# car_msp_breakouts.net
KiCad netlist of a schematic drawn in Altium Designer
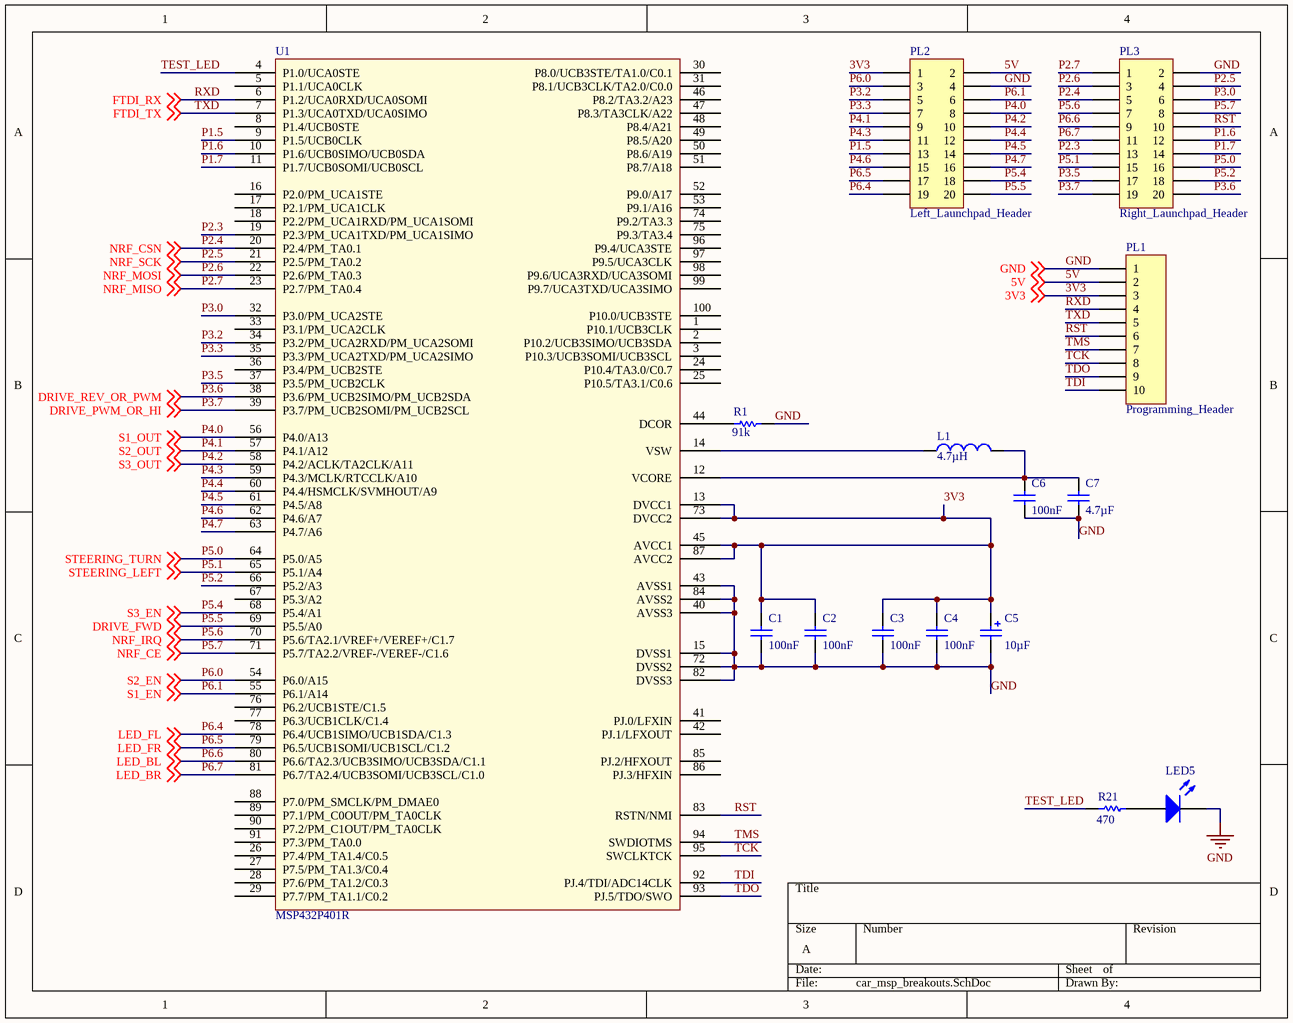
[diagram p0: car_msp_breakouts.SchDoc]

(export (version "E")
  (design (tool "Eeschema 10.0.6"))
  (components
    (comp (ref "C1")
      (value "100nF")
      (footprint "0805-C")
      (description "Capacitor")
      (fields (field (name "Comment") "Cap") (field (name "PUBLISHER") "Altium Limited"))
      (libsource (lib "Miscellaneous Devices") (part "Cap"))
    )
    (comp (ref "C2")
      (value "100nF")
      (footprint "0805-C")
      (description "Capacitor")
      (fields (field (name "Comment") "Cap") (field (name "PUBLISHER") "Altium Limited"))
      (libsource (lib "Miscellaneous Devices") (part "Cap"))
    )
    (comp (ref "C3")
      (value "100nF")
      (footprint "0805-C")
      (description "Capacitor")
      (fields (field (name "Comment") "Cap") (field (name "PUBLISHER") "Altium Limited"))
      (libsource (lib "Miscellaneous Devices") (part "Cap"))
    )
    (comp (ref "C4")
      (value "100nF")
      (footprint "0805-C")
      (description "Capacitor")
      (fields (field (name "Comment") "Cap") (field (name "PUBLISHER") "Altium Limited"))
      (libsource (lib "Miscellaneous Devices") (part "Cap"))
    )
    (comp (ref "C5")
      (value "10µF")
      (footprint "0805-TC")
      (description "Polarized Capacitor (Radial)")
      (fields (field (name "Comment") "Cap Pol1") (field (name "PUBLISHER") "Altium Limited"))
      (libsource (lib "Miscellaneous Devices") (part "Cap Pol1"))
    )
    (comp (ref "C6")
      (value "100nF")
      (footprint "0805-C")
      (description "Capacitor")
      (fields (field (name "Comment") "Cap") (field (name "PUBLISHER") "Altium Limited"))
      (libsource (lib "Miscellaneous Devices") (part "Cap"))
    )
    (comp (ref "C7")
      (value "4.7µF")
      (footprint "0805-C")
      (description "Capacitor")
      (fields (field (name "Comment") "Cap") (field (name "PUBLISHER") "Altium Limited"))
      (libsource (lib "Miscellaneous Devices") (part "Cap"))
    )
    (comp (ref "L1")
      (value "4.7µH")
      (footprint "0805-L")
      (description "Inductor")
      (fields (field (name "PUBLISHER") "Altium Limited"))
      (libsource (lib "Miscellaneous Devices") (part "Inductor"))
    )
    (comp (ref "LED5")
      (value "LED2")
      (footprint "0805-LED")
      (description "Typical RED, GREEN, YELLOW, AMBER GaAs LED")
      (fields (field (name "PUBLISHER") "Altium Limited"))
      (libsource (lib "Miscellaneous Devices") (part "LED2"))
    )
    (comp (ref "PL1")
      (value "Programming_Header")
      (footprint "HDR1X10")
      (description "Header, 10-Pin")
      (fields (field (name "PUBLISHER") "Altium Limited"))
      (libsource (lib "Miscellaneous Connectors") (part "Header 10"))
    )
    (comp (ref "PL2")
      (value "Left_Launchpad_Header")
      (footprint "HDR2X10")
      (description "Header, 10-Pin, Dual row")
      (fields (field (name "PUBLISHER") "Altium Limited"))
      (libsource (lib "Miscellaneous Connectors") (part "Header 10X2"))
    )
    (comp (ref "PL3")
      (value "Right_Launchpad_Header")
      (footprint "HDR2X10")
      (description "Header, 10-Pin, Dual row")
      (fields (field (name "PUBLISHER") "Altium Limited"))
      (libsource (lib "Miscellaneous Connectors") (part "Header 10X2"))
    )
    (comp (ref "R1")
      (value "91k")
      (footprint "0805-R")
      (description "Resistor")
      (fields (field (name "Comment") "Res1") (field (name "PUBLISHER") "Altium Limited"))
      (libsource (lib "Miscellaneous Devices") (part "Res1"))
    )
    (comp (ref "R21")
      (value "470")
      (footprint "0805-R")
      (description "Resistor")
      (fields (field (name "Comment") "Res1") (field (name "PUBLISHER") "Altium Limited"))
      (libsource (lib "Miscellaneous Devices") (part "Res1"))
    )
    (comp (ref "U1")
      (value "MSP432P401R")
      (footprint "TSQFP50P1600X1600X160-100N")
      (libsource (lib "MSP432") (part "MSP432"))
    )
  )
  (nets
    (net (code "1") (name "/P1.5") (class "Default")
      (node (ref "PL2") (pin "13") (pinfunction "13_13") (pintype "passive"))
      (node (ref "U1") (pin "9") (pinfunction "P1.5/UCB0CLK_9") (pintype "passive"))
    )
    (net (code "2") (name "/P1.6") (class "Default")
      (node (ref "PL3") (pin "12") (pinfunction "12_12") (pintype "passive"))
      (node (ref "U1") (pin "10") (pinfunction "P1.6/UCB0SIMO/UCB0SDA_10") (pintype "passive"))
    )
    (net (code "3") (name "/P1.7") (class "Default")
      (node (ref "PL3") (pin "14") (pinfunction "14_14") (pintype "passive"))
      (node (ref "U1") (pin "11") (pinfunction "P1.7/UCB0SOMI/UCB0SCL_11") (pintype "passive"))
    )
    (net (code "4") (name "/P2.3") (class "Default")
      (node (ref "PL3") (pin "13") (pinfunction "13_13") (pintype "passive"))
      (node (ref "U1") (pin "19") (pinfunction "P2.3/PM_UCA1TXD/PM_UCA1SIMO_19") (pintype "passive"))
    )
    (net (code "5") (name "/P3.0") (class "Default")
      (node (ref "PL3") (pin "6") (pinfunction "6_6") (pintype "passive"))
      (node (ref "U1") (pin "32") (pinfunction "P3.0/PM_UCA2STE_32") (pintype "passive"))
    )
    (net (code "6") (name "/P3.2") (class "Default")
      (node (ref "PL2") (pin "5") (pinfunction "5_5") (pintype "passive"))
      (node (ref "U1") (pin "34") (pinfunction "P3.2/PM_UCA2RXD/PM_UCA2SOMI_34") (pintype "passive"))
    )
    (net (code "7") (name "/P3.3") (class "Default")
      (node (ref "PL2") (pin "7") (pinfunction "7_7") (pintype "passive"))
      (node (ref "U1") (pin "35") (pinfunction "P3.3/PM_UCA2TXD/PM_UCA2SIMO_35") (pintype "passive"))
    )
    (net (code "8") (name "/P3.5") (class "Default")
      (node (ref "PL3") (pin "17") (pinfunction "17_17") (pintype "passive"))
      (node (ref "U1") (pin "37") (pinfunction "P3.5/PM_UCB2CLK_37") (pintype "passive"))
    )
    (net (code "9") (name "/P4.3") (class "Default")
      (node (ref "PL2") (pin "11") (pinfunction "11_11") (pintype "passive"))
      (node (ref "U1") (pin "59") (pinfunction "P4.3/MCLK/RTCCLK/A10_59") (pintype "passive"))
    )
    (net (code "10") (name "/P4.4") (class "Default")
      (node (ref "PL2") (pin "12") (pinfunction "12_12") (pintype "passive"))
      (node (ref "U1") (pin "60") (pinfunction "P4.4/HSMCLK/SVMHOUT/A9_60") (pintype "passive"))
    )
    (net (code "11") (name "/P4.5") (class "Default")
      (node (ref "PL2") (pin "14") (pinfunction "14_14") (pintype "passive"))
      (node (ref "U1") (pin "61") (pinfunction "P4.5/A8_61") (pintype "passive"))
    )
    (net (code "12") (name "/P4.6") (class "Default")
      (node (ref "PL2") (pin "15") (pinfunction "15_15") (pintype "passive"))
      (node (ref "U1") (pin "62") (pinfunction "P4.6/A7_62") (pintype "passive"))
    )
    (net (code "13") (name "/P4.7") (class "Default")
      (node (ref "PL2") (pin "16") (pinfunction "16_16") (pintype "passive"))
      (node (ref "U1") (pin "63") (pinfunction "P4.7/A6_63") (pintype "passive"))
    )
    (net (code "14") (name "/P5.2") (class "Default")
      (node (ref "PL3") (pin "18") (pinfunction "18_18") (pintype "passive"))
      (node (ref "U1") (pin "66") (pinfunction "P5.2/A3_66") (pintype "passive"))
    )
    (net (code "15") (name "/RST") (class "Default")
      (node (ref "PL1") (pin "6") (pinfunction "6_6") (pintype "passive"))
      (node (ref "PL3") (pin "10") (pinfunction "10_10") (pintype "passive"))
      (node (ref "U1") (pin "83") (pinfunction "RSTN/NMI_83") (pintype "passive"))
    )
    (net (code "16") (name "/TCK") (class "Default")
      (node (ref "PL1") (pin "8") (pinfunction "8_8") (pintype "passive"))
      (node (ref "U1") (pin "95") (pinfunction "SWCLKTCK_95") (pintype "passive"))
    )
    (net (code "17") (name "/TDI") (class "Default")
      (node (ref "PL1") (pin "10") (pinfunction "10_10") (pintype "passive"))
      (node (ref "U1") (pin "92") (pinfunction "PJ.4/TDI/ADC14CLK_92") (pintype "passive"))
    )
    (net (code "18") (name "/TDO") (class "Default")
      (node (ref "PL1") (pin "9") (pinfunction "9_9") (pintype "passive"))
      (node (ref "U1") (pin "93") (pinfunction "PJ.5/TDO/SWO_93") (pintype "passive"))
    )
    (net (code "19") (name "/TEST_LED") (class "Default")
      (node (ref "R21") (pin "1") (pinfunction "1_1") (pintype "passive"))
      (node (ref "U1") (pin "4") (pinfunction "P1.0/UCA0STE_4") (pintype "passive"))
    )
    (net (code "20") (name "/TMS") (class "Default")
      (node (ref "PL1") (pin "7") (pinfunction "7_7") (pintype "passive"))
      (node (ref "U1") (pin "94") (pinfunction "SWDIOTMS_94") (pintype "passive"))
    )
    (net (code "21") (name "3V3") (class "Default")
      (node (ref "C1") (pin "2") (pinfunction "2_2") (pintype "passive"))
      (node (ref "C2") (pin "2") (pinfunction "2_2") (pintype "passive"))
      (node (ref "C3") (pin "2") (pinfunction "2_2") (pintype "passive"))
      (node (ref "C4") (pin "2") (pinfunction "2_2") (pintype "passive"))
      (node (ref "C5") (pin "1") (pinfunction "1_1") (pintype "passive"))
      (node (ref "PL1") (pin "3") (pinfunction "3_3") (pintype "passive"))
      (node (ref "PL2") (pin "1") (pinfunction "1_1") (pintype "passive"))
      (node (ref "U1") (pin "13") (pinfunction "DVCC1_13") (pintype "passive"))
      (node (ref "U1") (pin "45") (pinfunction "AVCC1_45") (pintype "passive"))
      (node (ref "U1") (pin "73") (pinfunction "DVCC2_73") (pintype "passive"))
      (node (ref "U1") (pin "87") (pinfunction "AVCC2_87") (pintype "passive"))
    )
    (net (code "22") (name "5V") (class "Default")
      (node (ref "PL1") (pin "2") (pinfunction "2_2") (pintype "passive"))
      (node (ref "PL2") (pin "2") (pinfunction "2_2") (pintype "passive"))
    )
    (net (code "23") (name "DRIVE_FWD") (class "Default")
      (node (ref "PL2") (pin "20") (pinfunction "20_20") (pintype "passive"))
      (node (ref "U1") (pin "69") (pinfunction "P5.5/A0_69") (pintype "passive"))
    )
    (net (code "24") (name "DRIVE_PWM_OR_HI") (class "Default")
      (node (ref "PL3") (pin "19") (pinfunction "19_19") (pintype "passive"))
      (node (ref "U1") (pin "39") (pinfunction "P3.7/PM_UCB2SOMI/PM_UCB2SCL_39") (pintype "passive"))
    )
    (net (code "25") (name "DRIVE_REV_OR_PWM") (class "Default")
      (node (ref "PL3") (pin "20") (pinfunction "20_20") (pintype "passive"))
      (node (ref "U1") (pin "38") (pinfunction "P3.6/PM_UCB2SIMO/PM_UCB2SDA_38") (pintype "passive"))
    )
    (net (code "26") (name "FTDI_RX") (class "Default")
      (node (ref "PL1") (pin "4") (pinfunction "4_4") (pintype "passive"))
      (node (ref "U1") (pin "6") (pinfunction "P1.2/UCA0RXD/UCA0SOMI_6") (pintype "passive"))
    )
    (net (code "27") (name "FTDI_TX") (class "Default")
      (node (ref "PL1") (pin "5") (pinfunction "5_5") (pintype "passive"))
      (node (ref "U1") (pin "7") (pinfunction "P1.3/UCA0TXD/UCA0SIMO_7") (pintype "passive"))
    )
    (net (code "28") (name "GND") (class "Default")
      (node (ref "C1") (pin "1") (pinfunction "1_1") (pintype "passive"))
      (node (ref "C2") (pin "1") (pinfunction "1_1") (pintype "passive"))
      (node (ref "C3") (pin "1") (pinfunction "1_1") (pintype "passive"))
      (node (ref "C4") (pin "1") (pinfunction "1_1") (pintype "passive"))
      (node (ref "C5") (pin "2") (pinfunction "2_2") (pintype "passive"))
      (node (ref "C6") (pin "1") (pinfunction "1_1") (pintype "passive"))
      (node (ref "C7") (pin "1") (pinfunction "1_1") (pintype "passive"))
      (node (ref "LED5") (pin "2") (pinfunction "K_2") (pintype "passive"))
      (node (ref "PL1") (pin "1") (pinfunction "1_1") (pintype "passive"))
      (node (ref "PL2") (pin "4") (pinfunction "4_4") (pintype "passive"))
      (node (ref "PL3") (pin "2") (pinfunction "2_2") (pintype "passive"))
      (node (ref "R1") (pin "2") (pinfunction "2_2") (pintype "passive"))
      (node (ref "U1") (pin "15") (pinfunction "DVSS1_15") (pintype "passive"))
      (node (ref "U1") (pin "40") (pinfunction "AVSS3_40") (pintype "passive"))
      (node (ref "U1") (pin "43") (pinfunction "AVSS1_43") (pintype "passive"))
      (node (ref "U1") (pin "72") (pinfunction "DVSS2_72") (pintype "passive"))
      (node (ref "U1") (pin "82") (pinfunction "DVSS3_82") (pintype "passive"))
      (node (ref "U1") (pin "84") (pinfunction "AVSS2_84") (pintype "passive"))
    )
    (net (code "29") (name "LED_BL") (class "Default")
      (node (ref "PL3") (pin "9") (pinfunction "9_9") (pintype "passive"))
      (node (ref "U1") (pin "80") (pinfunction "P6.6/TA2.3/UCB3SIMO/UCB3SDA/C1.1_80") (pintype "passive"))
    )
    (net (code "30") (name "LED_BR") (class "Default")
      (node (ref "PL3") (pin "11") (pinfunction "11_11") (pintype "passive"))
      (node (ref "U1") (pin "81") (pinfunction "P6.7/TA2.4/UCB3SOMI/UCB3SCL/C1.0_81") (pintype "passive"))
    )
    (net (code "31") (name "LED_FL") (class "Default")
      (node (ref "PL2") (pin "19") (pinfunction "19_19") (pintype "passive"))
      (node (ref "U1") (pin "78") (pinfunction "P6.4/UCB1SIMO/UCB1SDA/C1.3_78") (pintype "passive"))
    )
    (net (code "32") (name "LED_FR") (class "Default")
      (node (ref "PL2") (pin "17") (pinfunction "17_17") (pintype "passive"))
      (node (ref "U1") (pin "79") (pinfunction "P6.5/UCB1SOMI/UCB1SCL/C1.2_79") (pintype "passive"))
    )
    (net (code "33") (name "NRF_CE") (class "Default")
      (node (ref "PL3") (pin "8") (pinfunction "8_8") (pintype "passive"))
      (node (ref "U1") (pin "71") (pinfunction "P5.7/TA2.2/VREF-/VEREF-/C1.6_71") (pintype "passive"))
    )
    (net (code "34") (name "NRF_CSN") (class "Default")
      (node (ref "PL3") (pin "5") (pinfunction "5_5") (pintype "passive"))
      (node (ref "U1") (pin "20") (pinfunction "P2.4/PM_TA0.1_20") (pintype "passive"))
    )
    (net (code "35") (name "NRF_IRQ") (class "Default")
      (node (ref "PL3") (pin "7") (pinfunction "7_7") (pintype "passive"))
      (node (ref "U1") (pin "70") (pinfunction "P5.6/TA2.1/VREF+/VEREF+/C1.7_70") (pintype "passive"))
    )
    (net (code "36") (name "NRF_MISO") (class "Default")
      (node (ref "PL3") (pin "1") (pinfunction "1_1") (pintype "passive"))
      (node (ref "U1") (pin "23") (pinfunction "P2.7/PM_TA0.4_23") (pintype "passive"))
    )
    (net (code "37") (name "NRF_MOSI") (class "Default")
      (node (ref "PL3") (pin "3") (pinfunction "3_3") (pintype "passive"))
      (node (ref "U1") (pin "22") (pinfunction "P2.6/PM_TA0.3_22") (pintype "passive"))
    )
    (net (code "38") (name "NRF_SCK") (class "Default")
      (node (ref "PL3") (pin "4") (pinfunction "4_4") (pintype "passive"))
      (node (ref "U1") (pin "21") (pinfunction "P2.5/PM_TA0.2_21") (pintype "passive"))
    )
    (net (code "39") (name "Net-(LED5-A)") (class "Default")
      (node (ref "LED5") (pin "1") (pinfunction "A_1") (pintype "passive"))
      (node (ref "R21") (pin "2") (pinfunction "2_2") (pintype "passive"))
    )
    (net (code "40") (name "Net-(U1-DCOR)") (class "Default")
      (node (ref "R1") (pin "1") (pinfunction "1_1") (pintype "passive"))
      (node (ref "U1") (pin "44") (pinfunction "DCOR_44") (pintype "passive"))
    )
    (net (code "41") (name "Net-(U1-VCORE)") (class "Default")
      (node (ref "C6") (pin "2") (pinfunction "2_2") (pintype "passive"))
      (node (ref "C7") (pin "2") (pinfunction "2_2") (pintype "passive"))
      (node (ref "L1") (pin "2") (pinfunction "2_2") (pintype "passive"))
      (node (ref "U1") (pin "12") (pinfunction "VCORE_12") (pintype "passive"))
    )
    (net (code "42") (name "Net-(U1-VSW)") (class "Default")
      (node (ref "L1") (pin "1") (pinfunction "1_1") (pintype "passive"))
      (node (ref "U1") (pin "14") (pinfunction "VSW_14") (pintype "passive"))
    )
    (net (code "43") (name "S1_EN") (class "Default")
      (node (ref "PL2") (pin "6") (pinfunction "6_6") (pintype "passive"))
      (node (ref "U1") (pin "55") (pinfunction "P6.1/A14_55") (pintype "passive"))
    )
    (net (code "44") (name "S1_OUT") (class "Default")
      (node (ref "PL2") (pin "8") (pinfunction "8_8") (pintype "passive"))
      (node (ref "U1") (pin "56") (pinfunction "P4.0/A13_56") (pintype "passive"))
    )
    (net (code "45") (name "S2_EN") (class "Default")
      (node (ref "PL2") (pin "3") (pinfunction "3_3") (pintype "passive"))
      (node (ref "U1") (pin "54") (pinfunction "P6.0/A15_54") (pintype "passive"))
    )
    (net (code "46") (name "S2_OUT") (class "Default")
      (node (ref "PL2") (pin "9") (pinfunction "9_9") (pintype "passive"))
      (node (ref "U1") (pin "57") (pinfunction "P4.1/A12_57") (pintype "passive"))
    )
    (net (code "47") (name "S3_EN") (class "Default")
      (node (ref "PL2") (pin "18") (pinfunction "18_18") (pintype "passive"))
      (node (ref "U1") (pin "68") (pinfunction "P5.4/A1_68") (pintype "passive"))
    )
    (net (code "48") (name "S3_OUT") (class "Default")
      (node (ref "PL2") (pin "10") (pinfunction "10_10") (pintype "passive"))
      (node (ref "U1") (pin "58") (pinfunction "P4.2/ACLK/TA2CLK/A11_58") (pintype "passive"))
    )
    (net (code "49") (name "STEERING_LEFT") (class "Default")
      (node (ref "PL3") (pin "15") (pinfunction "15_15") (pintype "passive"))
      (node (ref "U1") (pin "65") (pinfunction "P5.1/A4_65") (pintype "passive"))
    )
    (net (code "50") (name "STEERING_TURN") (class "Default")
      (node (ref "PL3") (pin "16") (pinfunction "16_16") (pintype "passive"))
      (node (ref "U1") (pin "64") (pinfunction "P5.0/A5_64") (pintype "passive"))
    )
    (net (code "51") (name "unconnected-(U1-P1.1{slash}UCA0CLK-Pad5)") (class "Default")
      (node (ref "U1") (pin "5") (pinfunction "P1.1/UCA0CLK_5") (pintype "passive"))
    )
    (net (code "52") (name "unconnected-(U1-P1.4{slash}UCB0STE-Pad8)") (class "Default")
      (node (ref "U1") (pin "8") (pinfunction "P1.4/UCB0STE_8") (pintype "passive"))
    )
    (net (code "53") (name "unconnected-(U1-P2.0{slash}PM_UCA1STE-Pad16)") (class "Default")
      (node (ref "U1") (pin "16") (pinfunction "P2.0/PM_UCA1STE_16") (pintype "passive"))
    )
    (net (code "54") (name "unconnected-(U1-P2.1{slash}PM_UCA1CLK-Pad17)") (class "Default")
      (node (ref "U1") (pin "17") (pinfunction "P2.1/PM_UCA1CLK_17") (pintype "passive"))
    )
    (net (code "55") (name "unconnected-(U1-P2.2{slash}PM_UCA1RXD{slash}PM_UCA1SOMI-Pad18)") (class "Default")
      (node (ref "U1") (pin "18") (pinfunction "P2.2/PM_UCA1RXD/PM_UCA1SOMI_18") (pintype "passive"))
    )
    (net (code "56") (name "unconnected-(U1-P3.1{slash}PM_UCA2CLK-Pad33)") (class "Default")
      (node (ref "U1") (pin "33") (pinfunction "P3.1/PM_UCA2CLK_33") (pintype "passive"))
    )
    (net (code "57") (name "unconnected-(U1-P3.4{slash}PM_UCB2STE-Pad36)") (class "Default")
      (node (ref "U1") (pin "36") (pinfunction "P3.4/PM_UCB2STE_36") (pintype "passive"))
    )
    (net (code "58") (name "unconnected-(U1-P5.3{slash}A2-Pad67)") (class "Default")
      (node (ref "U1") (pin "67") (pinfunction "P5.3/A2_67") (pintype "passive"))
    )
    (net (code "59") (name "unconnected-(U1-P6.2{slash}UCB1STE{slash}C1.5-Pad76)") (class "Default")
      (node (ref "U1") (pin "76") (pinfunction "P6.2/UCB1STE/C1.5_76") (pintype "passive"))
    )
    (net (code "60") (name "unconnected-(U1-P6.3{slash}UCB1CLK{slash}C1.4-Pad77)") (class "Default")
      (node (ref "U1") (pin "77") (pinfunction "P6.3/UCB1CLK/C1.4_77") (pintype "passive"))
    )
    (net (code "61") (name "unconnected-(U1-P7.0{slash}PM_SMCLK{slash}PM_DMAE0-Pad88)") (class "Default")
      (node (ref "U1") (pin "88") (pinfunction "P7.0/PM_SMCLK/PM_DMAE0_88") (pintype "passive"))
    )
    (net (code "62") (name "unconnected-(U1-P7.1{slash}PM_C0OUT{slash}PM_TA0CLK-Pad89)") (class "Default")
      (node (ref "U1") (pin "89") (pinfunction "P7.1/PM_C0OUT/PM_TA0CLK_89") (pintype "passive"))
    )
    (net (code "63") (name "unconnected-(U1-P7.2{slash}PM_C1OUT{slash}PM_TA0CLK-Pad90)") (class "Default")
      (node (ref "U1") (pin "90") (pinfunction "P7.2/PM_C1OUT/PM_TA0CLK_90") (pintype "passive"))
    )
    (net (code "64") (name "unconnected-(U1-P7.3{slash}PM_TA0.0-Pad91)") (class "Default")
      (node (ref "U1") (pin "91") (pinfunction "P7.3/PM_TA0.0_91") (pintype "passive"))
    )
    (net (code "65") (name "unconnected-(U1-P7.4{slash}PM_TA1.4{slash}C0.5-Pad26)") (class "Default")
      (node (ref "U1") (pin "26") (pinfunction "P7.4/PM_TA1.4/C0.5_26") (pintype "passive"))
    )
    (net (code "66") (name "unconnected-(U1-P7.5{slash}PM_TA1.3{slash}C0.4-Pad27)") (class "Default")
      (node (ref "U1") (pin "27") (pinfunction "P7.5/PM_TA1.3/C0.4_27") (pintype "passive"))
    )
    (net (code "67") (name "unconnected-(U1-P7.6{slash}PM_TA1.2{slash}C0.3-Pad28)") (class "Default")
      (node (ref "U1") (pin "28") (pinfunction "P7.6/PM_TA1.2/C0.3_28") (pintype "passive"))
    )
    (net (code "68") (name "unconnected-(U1-P7.7{slash}PM_TA1.1{slash}C0.2-Pad29)") (class "Default")
      (node (ref "U1") (pin "29") (pinfunction "P7.7/PM_TA1.1/C0.2_29") (pintype "passive"))
    )
    (net (code "69") (name "unconnected-(U1-P8.0{slash}UCB3STE{slash}TA1.0{slash}C0.1-Pad30)") (class "Default")
      (node (ref "U1") (pin "30") (pinfunction "P8.0/UCB3STE/TA1.0/C0.1_30") (pintype "passive"))
    )
    (net (code "70") (name "unconnected-(U1-P8.1{slash}UCB3CLK{slash}TA2.0{slash}C0.0-Pad31)") (class "Default")
      (node (ref "U1") (pin "31") (pinfunction "P8.1/UCB3CLK/TA2.0/C0.0_31") (pintype "passive"))
    )
    (net (code "71") (name "unconnected-(U1-P8.2{slash}TA3.2{slash}A23-Pad46)") (class "Default")
      (node (ref "U1") (pin "46") (pinfunction "P8.2/TA3.2/A23_46") (pintype "passive"))
    )
    (net (code "72") (name "unconnected-(U1-P8.3{slash}TA3CLK{slash}A22-Pad47)") (class "Default")
      (node (ref "U1") (pin "47") (pinfunction "P8.3/TA3CLK/A22_47") (pintype "passive"))
    )
    (net (code "73") (name "unconnected-(U1-P8.4{slash}A21-Pad48)") (class "Default")
      (node (ref "U1") (pin "48") (pinfunction "P8.4/A21_48") (pintype "passive"))
    )
    (net (code "74") (name "unconnected-(U1-P8.5{slash}A20-Pad49)") (class "Default")
      (node (ref "U1") (pin "49") (pinfunction "P8.5/A20_49") (pintype "passive"))
    )
    (net (code "75") (name "unconnected-(U1-P8.6{slash}A19-Pad50)") (class "Default")
      (node (ref "U1") (pin "50") (pinfunction "P8.6/A19_50") (pintype "passive"))
    )
    (net (code "76") (name "unconnected-(U1-P8.7{slash}A18-Pad51)") (class "Default")
      (node (ref "U1") (pin "51") (pinfunction "P8.7/A18_51") (pintype "passive"))
    )
    (net (code "77") (name "unconnected-(U1-P9.0{slash}A17-Pad52)") (class "Default")
      (node (ref "U1") (pin "52") (pinfunction "P9.0/A17_52") (pintype "passive"))
    )
    (net (code "78") (name "unconnected-(U1-P9.1{slash}A16-Pad53)") (class "Default")
      (node (ref "U1") (pin "53") (pinfunction "P9.1/A16_53") (pintype "passive"))
    )
    (net (code "79") (name "unconnected-(U1-P9.2{slash}TA3.3-Pad74)") (class "Default")
      (node (ref "U1") (pin "74") (pinfunction "P9.2/TA3.3_74") (pintype "passive"))
    )
    (net (code "80") (name "unconnected-(U1-P9.3{slash}TA3.4-Pad75)") (class "Default")
      (node (ref "U1") (pin "75") (pinfunction "P9.3/TA3.4_75") (pintype "passive"))
    )
    (net (code "81") (name "unconnected-(U1-P9.4{slash}UCA3STE-Pad96)") (class "Default")
      (node (ref "U1") (pin "96") (pinfunction "P9.4/UCA3STE_96") (pintype "passive"))
    )
    (net (code "82") (name "unconnected-(U1-P9.5{slash}UCA3CLK-Pad97)") (class "Default")
      (node (ref "U1") (pin "97") (pinfunction "P9.5/UCA3CLK_97") (pintype "passive"))
    )
    (net (code "83") (name "unconnected-(U1-P9.6{slash}UCA3RXD{slash}UCA3SOMI-Pad98)") (class "Default")
      (node (ref "U1") (pin "98") (pinfunction "P9.6/UCA3RXD/UCA3SOMI_98") (pintype "passive"))
    )
    (net (code "84") (name "unconnected-(U1-P9.7{slash}UCA3TXD{slash}UCA3SIMO-Pad99)") (class "Default")
      (node (ref "U1") (pin "99") (pinfunction "P9.7/UCA3TXD/UCA3SIMO_99") (pintype "passive"))
    )
    (net (code "85") (name "unconnected-(U1-P10.0{slash}UCB3STE-Pad100)") (class "Default")
      (node (ref "U1") (pin "100") (pinfunction "P10.0/UCB3STE_100") (pintype "passive"))
    )
    (net (code "86") (name "unconnected-(U1-P10.1{slash}UCB3CLK-Pad1)") (class "Default")
      (node (ref "U1") (pin "1") (pinfunction "P10.1/UCB3CLK_1") (pintype "passive"))
    )
    (net (code "87") (name "unconnected-(U1-P10.2{slash}UCB3SIMO{slash}UCB3SDA-Pad2)") (class "Default")
      (node (ref "U1") (pin "2") (pinfunction "P10.2/UCB3SIMO/UCB3SDA_2") (pintype "passive"))
    )
    (net (code "88") (name "unconnected-(U1-P10.3{slash}UCB3SOMI{slash}UCB3SCL-Pad3)") (class "Default")
      (node (ref "U1") (pin "3") (pinfunction "P10.3/UCB3SOMI/UCB3SCL_3") (pintype "passive"))
    )
    (net (code "89") (name "unconnected-(U1-P10.4{slash}TA3.0{slash}C0.7-Pad24)") (class "Default")
      (node (ref "U1") (pin "24") (pinfunction "P10.4/TA3.0/C0.7_24") (pintype "passive"))
    )
    (net (code "90") (name "unconnected-(U1-P10.5{slash}TA3.1{slash}C0.6-Pad25)") (class "Default")
      (node (ref "U1") (pin "25") (pinfunction "P10.5/TA3.1/C0.6_25") (pintype "passive"))
    )
    (net (code "91") (name "unconnected-(U1-PJ.0{slash}LFXIN-Pad41)") (class "Default")
      (node (ref "U1") (pin "41") (pinfunction "PJ.0/LFXIN_41") (pintype "passive"))
    )
    (net (code "92") (name "unconnected-(U1-PJ.1{slash}LFXOUT-Pad42)") (class "Default")
      (node (ref "U1") (pin "42") (pinfunction "PJ.1/LFXOUT_42") (pintype "passive"))
    )
    (net (code "93") (name "unconnected-(U1-PJ.2{slash}HFXOUT-Pad85)") (class "Default")
      (node (ref "U1") (pin "85") (pinfunction "PJ.2/HFXOUT_85") (pintype "passive"))
    )
    (net (code "94") (name "unconnected-(U1-PJ.3{slash}HFXIN-Pad86)") (class "Default")
      (node (ref "U1") (pin "86") (pinfunction "PJ.3/HFXIN_86") (pintype "passive"))
    )
  )
)
